# SoC_Connector.net
KiCad netlist of a schematic drawn in Altium Designer
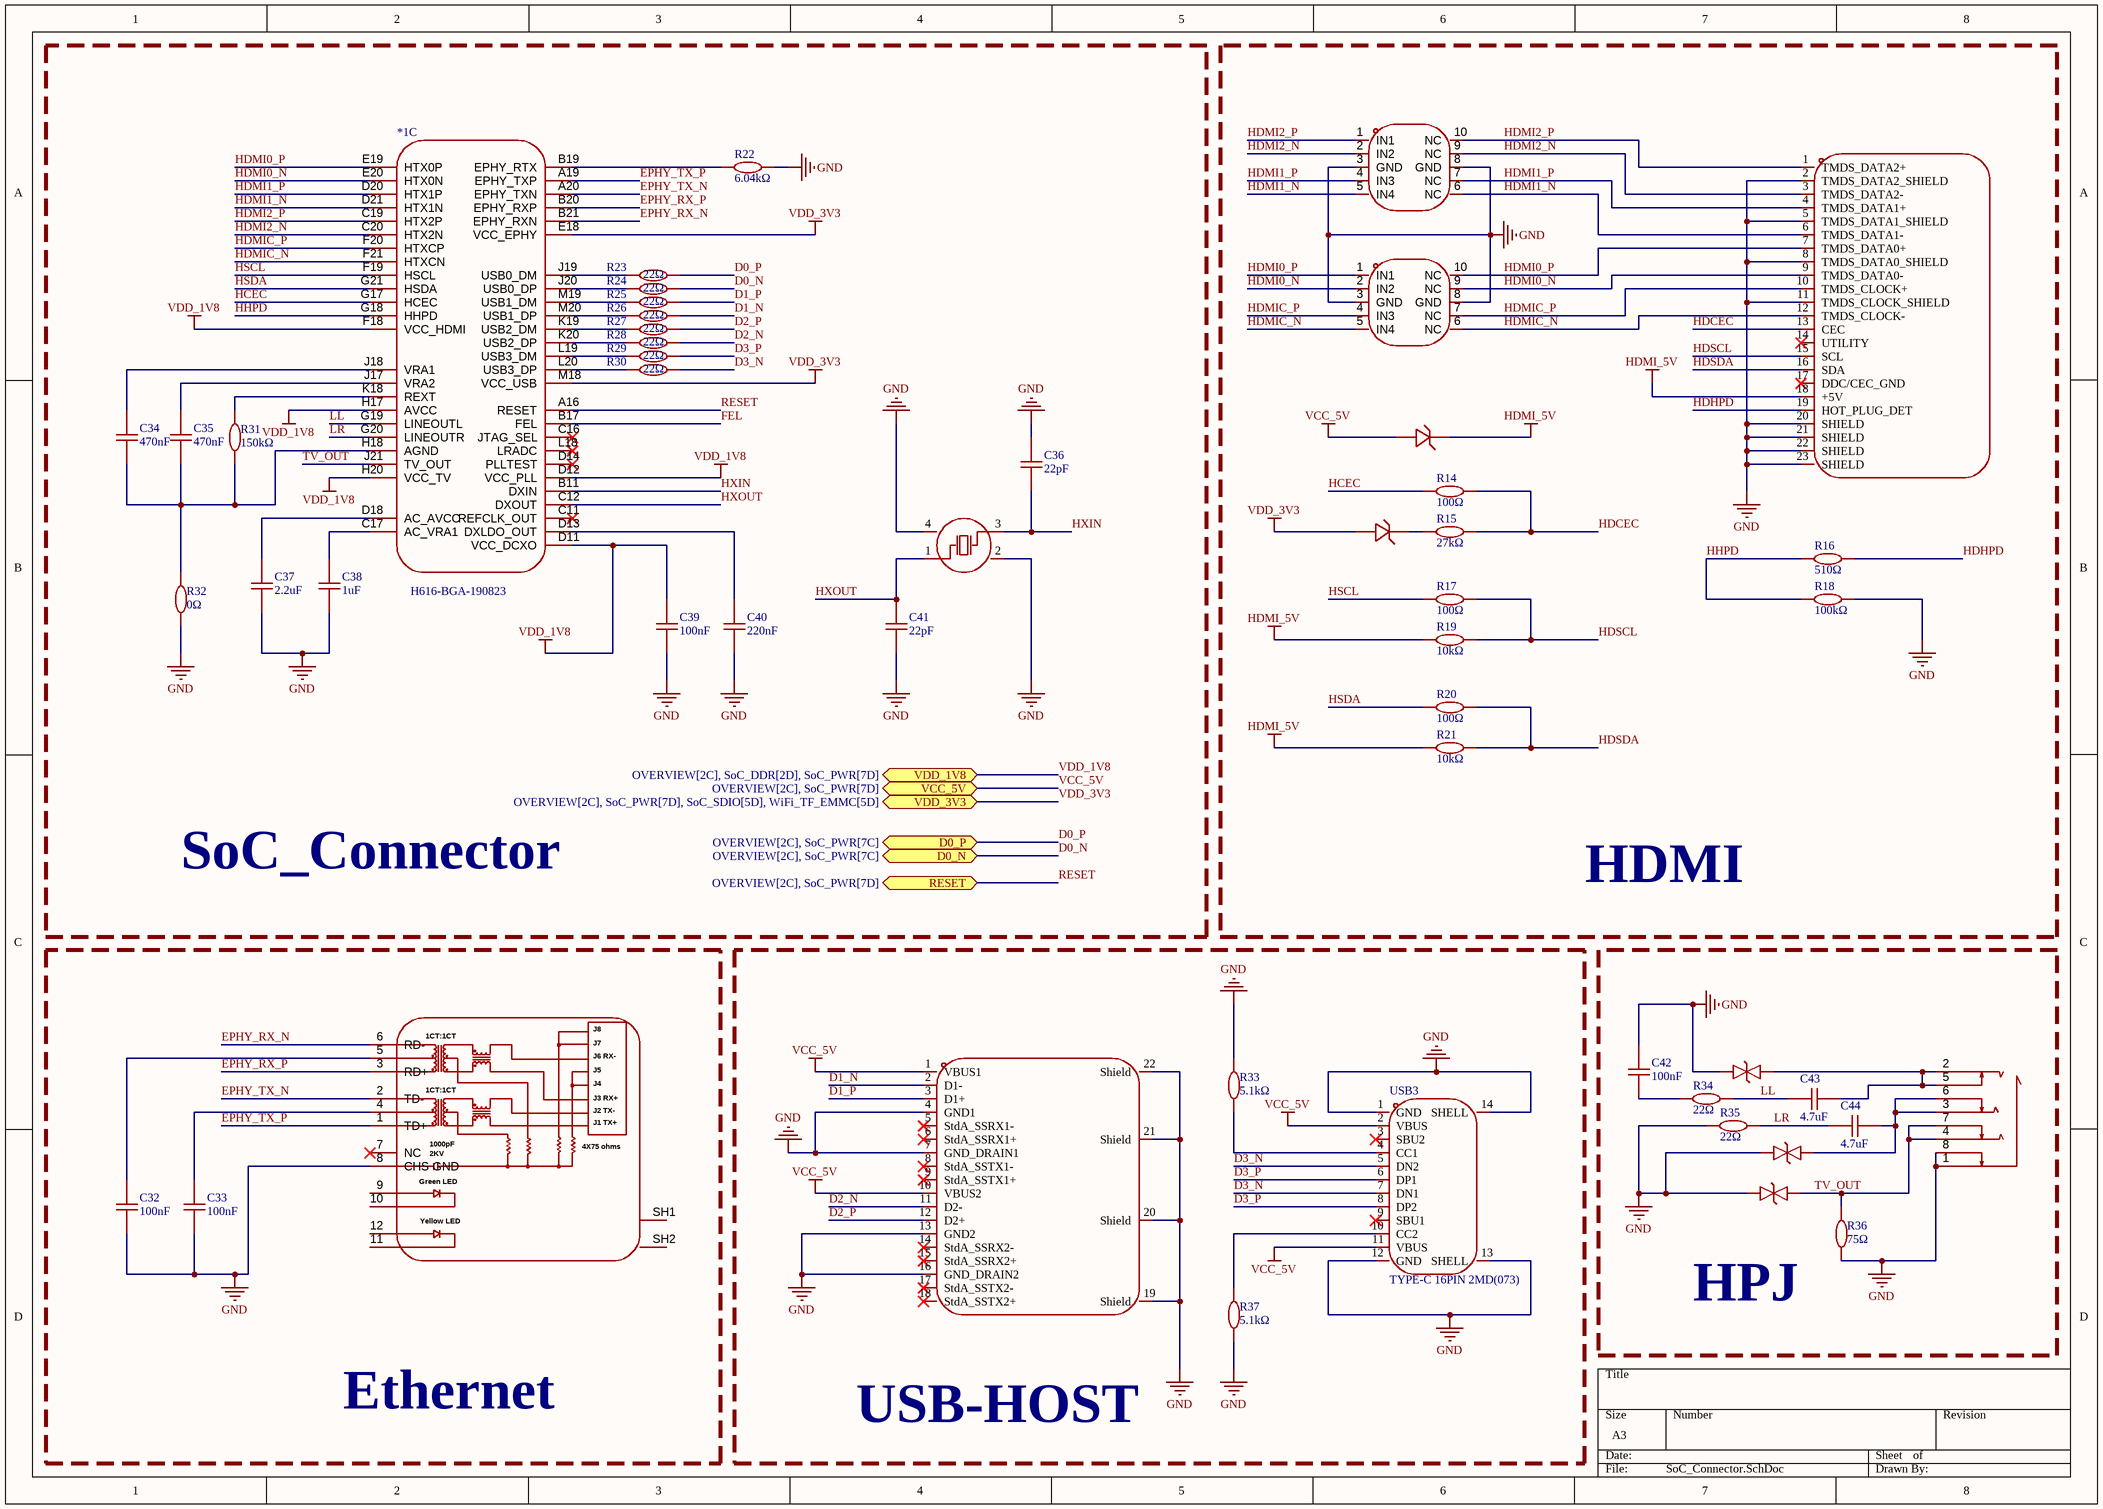
[diagram p0: SoC_Connector.SchDoc]

(export (version "E")
  (design (tool "Eeschema 10.0.6"))
  (components
    (comp (ref "*1")
      (value "H616-BGA-190823")
      (footprint "BGA-284_L14.0-W12.0-P0.65-TL")
      (description "Allwinner H616")
      (libsource (lib "IC") (part "H616-BGA-190823"))
    )
    (comp (ref "AUDIO1")
      (value "PJ-3930-8A")
      (footprint "AUDIO-TH_PJ-3930-8A")
      (description "3.5mm耳机座")
      (libsource (lib "Connector") (part "PJ-3930-8A"))
    )
    (comp (ref "C32")
      (value "100nF")
      (footprint "C0402")
      (description "50V 100nF X7R ±10% 0402 Ceramic Capacitors ROHS")
      (libsource (lib "RLC") (part "100nF"))
    )
    (comp (ref "C33")
      (value "100nF")
      (footprint "C0402")
      (description "50V 100nF X7R ±10% 0402 Ceramic Capacitors ROHS")
      (libsource (lib "RLC") (part "100nF"))
    )
    (comp (ref "C34")
      (value "470nF")
      (footprint "C0402")
      (description "25V 470nF X5R ±10% 0402 Ceramic Capacitors ROHS")
      (libsource (lib "RLC") (part "470nF"))
    )
    (comp (ref "C35")
      (value "470nF")
      (footprint "C0402")
      (description "25V 470nF X5R ±10% 0402 Ceramic Capacitors ROHS")
      (libsource (lib "RLC") (part "470nF"))
    )
    (comp (ref "C36")
      (value "22pF")
      (footprint "C0402")
      (description "50V 22pF C0G ±5% 0402 Ceramic Capacitors ROHS")
      (libsource (lib "RLC") (part "22pF"))
    )
    (comp (ref "C37")
      (value "2.2uF")
      (footprint "C0402")
      (description "50V 2.2uF NP0 0402 Ceramic Capacitors ROHS")
      (libsource (lib "RLC") (part "2.2uF"))
    )
    (comp (ref "C38")
      (value "1uF")
      (footprint "C0402")
      (description "50V 1uF X5R ±10% 0402 Ceramic Capacitors ROHS")
      (libsource (lib "RLC") (part "1uF"))
    )
    (comp (ref "C39")
      (value "100nF")
      (footprint "C0402")
      (description "50V 100nF X7R ±10% 0402 Ceramic Capacitors ROHS")
      (libsource (lib "RLC") (part "100nF"))
    )
    (comp (ref "C40")
      (value "220nF")
      (footprint "C0402")
      (description "16V 220nF X7R ±10% 0402 Ceramic Capacitors ROHS")
      (libsource (lib "RLC") (part "220nF"))
    )
    (comp (ref "C41")
      (value "22pF")
      (footprint "C0402")
      (description "50V 22pF C0G ±5% 0402 Ceramic Capacitors ROHS")
      (libsource (lib "RLC") (part "22pF"))
    )
    (comp (ref "C42")
      (value "100nF")
      (footprint "C0402")
      (description "50V 100nF X7R ±10% 0402 Ceramic Capacitors ROHS")
      (libsource (lib "RLC") (part "100nF"))
    )
    (comp (ref "C43")
      (value "4.7uF")
      (footprint "C0402")
      (description "10V 4.7uF X5R ±20% 0402 Ceramic Capacitors ROHS")
      (libsource (lib "RLC") (part "4.7uF"))
    )
    (comp (ref "C44")
      (value "4.7uF")
      (footprint "C0402")
      (description "10V 4.7uF X5R ±20% 0402 Ceramic Capacitors ROHS")
      (libsource (lib "RLC") (part "4.7uF"))
    )
    (comp (ref "CN1")
      (value "KH-HDMI-19P-Cu")
      (footprint "HDMI-SMD_KH-HDMI-19P-CU")
      (description "HDMI-A SMD USB, DVI, HDMI Connector Assemblies ROHS")
      (fields (field (name "MANUFACTURER") "kinghelm(金航标)"))
      (libsource (lib "Connector") (part "KH-HDMI-19P-Cu"))
    )
    (comp (ref "D2")
      (value "RClamp0524PATCT")
      (footprint "SLP2510P8_L2.5-W1.0-P0.50-BL")
      (description "ESD 5V截止 峰值浪涌电流：5A@8/20us")
      (libsource (lib "LED") (part "RClamp0524PATCT"))
    )
    (comp (ref "D3")
      (value "RClamp0524PATCT")
      (footprint "SLP2510P8_L2.5-W1.0-P0.50-BL")
      (description "ESD 5V截止 峰值浪涌电流：5A@8/20us")
      (libsource (lib "LED") (part "RClamp0524PATCT"))
    )
    (comp (ref "D4")
      (value "DSK24")
      (footprint "SOD-123FL_L2.7-W1.8-LS3.8-RD")
      (description "电压:40V 电流:2A")
      (fields (field (name "MANUFACTURER") "Littelfuse(美国力特)") (field (name "MANUFACTURER PART") "SMAJ5.0A"))
      (libsource (lib "LED") (part "DSK24"))
    )
    (comp (ref "D5")
      (value "DSK24")
      (footprint "SOD-123FL_L2.7-W1.8-LS3.8-RD")
      (description "电压:40V 电流:2A")
      (fields (field (name "MANUFACTURER") "Littelfuse(美国力特)") (field (name "MANUFACTURER PART") "SMAJ5.0A"))
      (libsource (lib "LED") (part "DSK24"))
    )
    (comp (ref "J1")
      (value "HR911105A_C12074")
      (footprint "RJ45-TH_HR911105A")
      (description "Ethernet 弯插 带LED")
      (libsource (lib "Connector") (part "HR911105A_C12074"))
    )
    (comp (ref "R14")
      (value "100Ω")
      (footprint "R0402")
      (description "100Ω 62.5mW 50V ±100ppm/℃ Thick Film Resistor ±1% 0402 Chip Resistor - Surface Mount ROHS")
      (libsource (lib "RLC") (part "100Ω"))
    )
    (comp (ref "R15")
      (value "27kΩ")
      (footprint "R0402")
      (description "小尺寸、重量轻。降低组装成本,与贴片机匹配。适用于波峰焊和回流焊")
      (libsource (lib "RLC") (part "27kΩ"))
    )
    (comp (ref "R16")
      (value "510Ω")
      (footprint "R0402")
      (description "510Ω 62.5mW 50V ±100ppm/℃ Thick Film Resistor ±1% 0402 Chip Resistor - Surface Mount ROHS")
      (libsource (lib "RLC") (part "510Ω"))
    )
    (comp (ref "R17")
      (value "100Ω")
      (footprint "R0402")
      (description "100Ω 62.5mW 50V ±100ppm/℃ Thick Film Resistor ±1% 0402 Chip Resistor - Surface Mount ROHS")
      (libsource (lib "RLC") (part "100Ω"))
    )
    (comp (ref "R18")
      (value "100kΩ")
      (footprint "R0402")
      (description "100kΩ 62.5mW 50V ±100ppm/℃ Thick Film Resistor ±1% 0402 Chip Resistor - Surface Mount ROHS")
      (libsource (lib "RLC") (part "100kΩ"))
    )
    (comp (ref "R19")
      (value "10kΩ")
      (footprint "R0402")
      (description "62.5mW 10kΩ 50V ±100ppm/℃ Thick Film Resistor ±1% 0402 Chip Resistor - Surface Mount ROHS")
      (libsource (lib "RLC") (part "10kΩ"))
    )
    (comp (ref "R20")
      (value "100Ω")
      (footprint "R0402")
      (description "100Ω 62.5mW 50V ±100ppm/℃ Thick Film Resistor ±1% 0402 Chip Resistor - Surface Mount ROHS")
      (libsource (lib "RLC") (part "100Ω"))
    )
    (comp (ref "R21")
      (value "10kΩ")
      (footprint "R0402")
      (description "62.5mW 10kΩ 50V ±100ppm/℃ Thick Film Resistor ±1% 0402 Chip Resistor - Surface Mount ROHS")
      (libsource (lib "RLC") (part "10kΩ"))
    )
    (comp (ref "R22")
      (value "6.04kΩ")
      (footprint "R0402")
      (description "6.04kΩ 62.5mW 50V ±100ppm/℃ Thick Film Resistor ±1% 0402 Chip Resistor - Surface Mount ROHS")
      (libsource (lib "RLC") (part "6.04kΩ"))
    )
    (comp (ref "R23")
      (value "22Ω")
      (footprint "R0402")
      (description "小尺寸、重量轻。降低组装成本,与贴片机匹配。适用于波峰焊和回流焊")
      (libsource (lib "RLC") (part "22Ω"))
    )
    (comp (ref "R24")
      (value "22Ω")
      (footprint "R0402")
      (description "小尺寸、重量轻。降低组装成本,与贴片机匹配。适用于波峰焊和回流焊")
      (libsource (lib "RLC") (part "22Ω"))
    )
    (comp (ref "R25")
      (value "22Ω")
      (footprint "R0402")
      (description "小尺寸、重量轻。降低组装成本,与贴片机匹配。适用于波峰焊和回流焊")
      (libsource (lib "RLC") (part "22Ω"))
    )
    (comp (ref "R26")
      (value "22Ω")
      (footprint "R0402")
      (description "小尺寸、重量轻。降低组装成本,与贴片机匹配。适用于波峰焊和回流焊")
      (libsource (lib "RLC") (part "22Ω"))
    )
    (comp (ref "R27")
      (value "22Ω")
      (footprint "R0402")
      (description "小尺寸、重量轻。降低组装成本,与贴片机匹配。适用于波峰焊和回流焊")
      (libsource (lib "RLC") (part "22Ω"))
    )
    (comp (ref "R28")
      (value "22Ω")
      (footprint "R0402")
      (description "小尺寸、重量轻。降低组装成本,与贴片机匹配。适用于波峰焊和回流焊")
      (libsource (lib "RLC") (part "22Ω"))
    )
    (comp (ref "R29")
      (value "22Ω")
      (footprint "R0402")
      (description "小尺寸、重量轻。降低组装成本,与贴片机匹配。适用于波峰焊和回流焊")
      (libsource (lib "RLC") (part "22Ω"))
    )
    (comp (ref "R30")
      (value "22Ω")
      (footprint "R0402")
      (description "小尺寸、重量轻。降低组装成本,与贴片机匹配。适用于波峰焊和回流焊")
      (libsource (lib "RLC") (part "22Ω"))
    )
    (comp (ref "R31")
      (value "150kΩ")
      (footprint "R0402")
      (description "62.5mW 150kΩ 50V ±100ppm/℃ Thick Film Resistor ±1% 0402 Chip Resistor - Surface Mount ROHS")
      (libsource (lib "RLC") (part "150kΩ"))
    )
    (comp (ref "R32")
      (value "0Ω")
      (footprint "R0402")
      (description "0Ω 62.5mW 50V Thick Film Resistor ±1% 0402 Chip Resistor - Surface Mount ROHS")
      (libsource (lib "RLC") (part "0Ω"))
    )
    (comp (ref "R33")
      (value "5.1kΩ")
      (footprint "R0402")
      (description "5.1kΩ 62.5mW 50V ±100ppm/℃ Thick Film Resistor ±1% 0402 Chip Resistor - Surface Mount ROHS")
      (libsource (lib "RLC") (part "5.1kΩ"))
    )
    (comp (ref "R34")
      (value "22Ω")
      (footprint "R0402")
      (description "小尺寸、重量轻。降低组装成本,与贴片机匹配。适用于波峰焊和回流焊")
      (libsource (lib "RLC") (part "22Ω"))
    )
    (comp (ref "R35")
      (value "22Ω")
      (footprint "R0402")
      (description "小尺寸、重量轻。降低组装成本,与贴片机匹配。适用于波峰焊和回流焊")
      (libsource (lib "RLC") (part "22Ω"))
    )
    (comp (ref "R36")
      (value "75Ω")
      (footprint "R0402")
      (description "小尺寸、重量轻。降低组装成本,与贴片机匹配。适用于波峰焊和回流焊")
      (libsource (lib "RLC") (part "75Ω"))
    )
    (comp (ref "R37")
      (value "5.1kΩ")
      (footprint "R0402")
      (description "5.1kΩ 62.5mW 50V ±100ppm/℃ Thick Film Resistor ±1% 0402 Chip Resistor - Surface Mount ROHS")
      (libsource (lib "RLC") (part "5.1kΩ"))
    )
    (comp (ref "U3")
      (value "ESD5451N")
      (footprint "DFN1006-2L-BI")
      (description "9A 9.8V 8V Bidirectional 5V DFN1006-2L TVS Diodes ROHS")
      (fields (field (name "MANUFACTURER") "HXY MOSFET(华轩阳电子)"))
      (libsource (lib "LED") (part "ESD5451N_C5261080"))
    )
    (comp (ref "U4")
      (value "ESD5451N")
      (footprint "DFN1006-2L-BI")
      (description "9A 9.8V 8V Bidirectional 5V DFN1006-2L TVS Diodes ROHS")
      (fields (field (name "MANUFACTURER") "HXY MOSFET(华轩阳电子)"))
      (libsource (lib "LED") (part "ESD5451N_C5261080"))
    )
    (comp (ref "U5")
      (value "ESD5451N")
      (footprint "DFN1006-2L-BI")
      (description "9A 9.8V 8V Bidirectional 5V DFN1006-2L TVS Diodes ROHS")
      (fields (field (name "MANUFACTURER") "HXY MOSFET(华轩阳电子)"))
      (libsource (lib "LED") (part "ESD5451N_C5261080"))
    )
    (comp (ref "USB2")
      (value "USB-303WSD-BRY")
      (footprint "USB-A-TH_XUNPU_USB-303WSD-BRY")
      (description "USB 3.0 2 9Px2 -30℃~+85℃ Type-A Through Hole,Right Angle USB, DVI, HDMI Connector Assemblies ROHS")
      (fields (field (name "MANUFACTURER") "XUNPU(讯普)"))
      (libsource (lib "Connector") (part "USB-303WSD-BRY"))
    )
    (comp (ref "USB3")
      (value "TYPE-C 16PIN 2MD(073)")
      (footprint "USB-C-SMD_TYPE-C-6PIN-2MD-073")
      (description "16pin type-c")
      (libsource (lib "Connector") (part "TYPE-C 16PIN 2MD(073)"))
    )
    (comp (ref "X1")
      (value "24MHz")
      (footprint "CRYSTAL-SMD_4P-L3.2-W2.5-BL")
      (description "Crystal Oscillator 12pF SMD3225-4P Crystals ROHS")
      (fields (field (name "MANUFACTURER") "YXC(扬兴晶振)") (field (name "MANUFACTURER PART") "X322524MOB4SI"))
      (libsource (lib "OSC") (part "X322524MOB4SI"))
    )
  )
  (nets
    (net (code "1") (name "/D0_N") (class "Default")
      (node (ref "R24") (pin "2") (pinfunction "2_2") (pintype "passive"))
    )
    (net (code "2") (name "/D0_P") (class "Default")
      (node (ref "R23") (pin "2") (pinfunction "2_2") (pintype "passive"))
    )
    (net (code "3") (name "/D1_N") (class "Default")
      (node (ref "R26") (pin "2") (pinfunction "2_2") (pintype "passive"))
      (node (ref "USB2") (pin "2") (pinfunction "D1-_2") (pintype "passive"))
    )
    (net (code "4") (name "/D1_P") (class "Default")
      (node (ref "R25") (pin "2") (pinfunction "2_2") (pintype "passive"))
      (node (ref "USB2") (pin "3") (pinfunction "D1+_3") (pintype "passive"))
    )
    (net (code "5") (name "/D2_N") (class "Default")
      (node (ref "R28") (pin "2") (pinfunction "2_2") (pintype "passive"))
      (node (ref "USB2") (pin "11") (pinfunction "D2-_11") (pintype "passive"))
    )
    (net (code "6") (name "/D2_P") (class "Default")
      (node (ref "R27") (pin "2") (pinfunction "2_2") (pintype "passive"))
      (node (ref "USB2") (pin "12") (pinfunction "D2+_12") (pintype "passive"))
    )
    (net (code "7") (name "/D3_N") (class "Default")
      (node (ref "R30") (pin "2") (pinfunction "2_2") (pintype "passive"))
      (node (ref "USB3") (pin "5") (pinfunction "DN2_5") (pintype "passive"))
      (node (ref "USB3") (pin "7") (pinfunction "DN1_7") (pintype "passive"))
    )
    (net (code "8") (name "/D3_P") (class "Default")
      (node (ref "R29") (pin "2") (pinfunction "2_2") (pintype "passive"))
      (node (ref "USB3") (pin "6") (pinfunction "DP1_6") (pintype "passive"))
      (node (ref "USB3") (pin "8") (pinfunction "DP2_8") (pintype "passive"))
    )
    (net (code "9") (name "/EPHY_RX_N") (class "Default")
      (node (ref "*1") (pin "B21") (pinfunction "EPHY_RXN_B21") (pintype "passive"))
      (node (ref "J1") (pin "6") (pinfunction "RD-_6") (pintype "passive"))
    )
    (net (code "10") (name "/EPHY_RX_P") (class "Default")
      (node (ref "*1") (pin "B20") (pinfunction "EPHY_RXP_B20") (pintype "passive"))
      (node (ref "J1") (pin "3") (pinfunction "RD+_3") (pintype "passive"))
    )
    (net (code "11") (name "/EPHY_TX_N") (class "Default")
      (node (ref "*1") (pin "A20") (pinfunction "EPHY_TXN_A20") (pintype "passive"))
      (node (ref "J1") (pin "2") (pinfunction "TD-_2") (pintype "passive"))
    )
    (net (code "12") (name "/EPHY_TX_P") (class "Default")
      (node (ref "*1") (pin "A19") (pinfunction "EPHY_TXP_A19") (pintype "passive"))
      (node (ref "J1") (pin "1") (pinfunction "TD+_1") (pintype "passive"))
    )
    (net (code "13") (name "/FEL") (class "Default")
      (node (ref "*1") (pin "B17") (pinfunction "FEL_B17") (pintype "passive"))
    )
    (net (code "14") (name "/HCEC") (class "Default")
      (node (ref "*1") (pin "G17") (pinfunction "HCEC_G17") (pintype "passive"))
      (node (ref "R14") (pin "1") (pinfunction "1_1") (pintype "passive"))
    )
    (net (code "15") (name "/HDCEC") (class "Default")
      (node (ref "CN1") (pin "13") (pinfunction "CEC_13") (pintype "passive"))
      (node (ref "R14") (pin "2") (pinfunction "2_2") (pintype "passive"))
      (node (ref "R15") (pin "2") (pinfunction "2_2") (pintype "passive"))
    )
    (net (code "16") (name "/HDHPD") (class "Default")
      (node (ref "CN1") (pin "19") (pinfunction "HOT_PLUG_DET_19") (pintype "passive"))
      (node (ref "R16") (pin "2") (pinfunction "2_2") (pintype "passive"))
    )
    (net (code "17") (name "/HDMI0_N") (class "Default")
      (node (ref "*1") (pin "E20") (pinfunction "HTX0N_E20") (pintype "passive"))
      (node (ref "CN1") (pin "9") (pinfunction "TMDS_DATA0-_9") (pintype "passive"))
      (node (ref "D3") (pin "2") (pinfunction "IN2_2") (pintype "passive"))
      (node (ref "D3") (pin "9") (pinfunction "NC_9") (pintype "passive"))
    )
    (net (code "18") (name "/HDMI0_P") (class "Default")
      (node (ref "*1") (pin "E19") (pinfunction "HTX0P_E19") (pintype "passive"))
      (node (ref "CN1") (pin "7") (pinfunction "TMDS_DATA0+_7") (pintype "passive"))
      (node (ref "D3") (pin "1") (pinfunction "IN1_1") (pintype "passive"))
      (node (ref "D3") (pin "10") (pinfunction "NC_10") (pintype "passive"))
    )
    (net (code "19") (name "/HDMI1_N") (class "Default")
      (node (ref "*1") (pin "D21") (pinfunction "HTX1N_D21") (pintype "passive"))
      (node (ref "CN1") (pin "6") (pinfunction "TMDS_DATA1-_6") (pintype "passive"))
      (node (ref "D2") (pin "5") (pinfunction "IN4_5") (pintype "passive"))
      (node (ref "D2") (pin "6") (pinfunction "NC_6") (pintype "passive"))
    )
    (net (code "20") (name "/HDMI1_P") (class "Default")
      (node (ref "*1") (pin "D20") (pinfunction "HTX1P_D20") (pintype "passive"))
      (node (ref "CN1") (pin "4") (pinfunction "TMDS_DATA1+_4") (pintype "passive"))
      (node (ref "D2") (pin "4") (pinfunction "IN3_4") (pintype "passive"))
      (node (ref "D2") (pin "7") (pinfunction "NC_7") (pintype "passive"))
    )
    (net (code "21") (name "/HDMI2_N") (class "Default")
      (node (ref "*1") (pin "C20") (pinfunction "HTX2N_C20") (pintype "passive"))
      (node (ref "CN1") (pin "3") (pinfunction "TMDS_DATA2-_3") (pintype "passive"))
      (node (ref "D2") (pin "2") (pinfunction "IN2_2") (pintype "passive"))
      (node (ref "D2") (pin "9") (pinfunction "NC_9") (pintype "passive"))
    )
    (net (code "22") (name "/HDMI2_P") (class "Default")
      (node (ref "*1") (pin "C19") (pinfunction "HTX2P_C19") (pintype "passive"))
      (node (ref "CN1") (pin "1") (pinfunction "TMDS_DATA2+_1") (pintype "passive"))
      (node (ref "D2") (pin "1") (pinfunction "IN1_1") (pintype "passive"))
      (node (ref "D2") (pin "10") (pinfunction "NC_10") (pintype "passive"))
    )
    (net (code "23") (name "/HDMIC_N") (class "Default")
      (node (ref "*1") (pin "F21") (pinfunction "HTXCN_F21") (pintype "passive"))
      (node (ref "CN1") (pin "12") (pinfunction "TMDS_CLOCK-_12") (pintype "passive"))
      (node (ref "D3") (pin "5") (pinfunction "IN4_5") (pintype "passive"))
      (node (ref "D3") (pin "6") (pinfunction "NC_6") (pintype "passive"))
    )
    (net (code "24") (name "/HDMIC_P") (class "Default")
      (node (ref "*1") (pin "F20") (pinfunction "HTXCP_F20") (pintype "passive"))
      (node (ref "CN1") (pin "10") (pinfunction "TMDS_CLOCK+_10") (pintype "passive"))
      (node (ref "D3") (pin "4") (pinfunction "IN3_4") (pintype "passive"))
      (node (ref "D3") (pin "7") (pinfunction "NC_7") (pintype "passive"))
    )
    (net (code "25") (name "/HDSCL") (class "Default")
      (node (ref "CN1") (pin "15") (pinfunction "SCL_15") (pintype "passive"))
      (node (ref "R17") (pin "2") (pinfunction "2_2") (pintype "passive"))
      (node (ref "R19") (pin "2") (pinfunction "2_2") (pintype "passive"))
    )
    (net (code "26") (name "/HDSDA") (class "Default")
      (node (ref "CN1") (pin "16") (pinfunction "SDA_16") (pintype "passive"))
      (node (ref "R20") (pin "2") (pinfunction "2_2") (pintype "passive"))
      (node (ref "R21") (pin "2") (pinfunction "2_2") (pintype "passive"))
    )
    (net (code "27") (name "/HHPD") (class "Default")
      (node (ref "*1") (pin "G18") (pinfunction "HHPD_G18") (pintype "passive"))
      (node (ref "R16") (pin "1") (pinfunction "1_1") (pintype "passive"))
      (node (ref "R18") (pin "1") (pinfunction "1_1") (pintype "passive"))
    )
    (net (code "28") (name "/HSCL") (class "Default")
      (node (ref "*1") (pin "F19") (pinfunction "HSCL_F19") (pintype "passive"))
      (node (ref "R17") (pin "1") (pinfunction "1_1") (pintype "passive"))
    )
    (net (code "29") (name "/HSDA") (class "Default")
      (node (ref "*1") (pin "G21") (pinfunction "HSDA_G21") (pintype "passive"))
      (node (ref "R20") (pin "1") (pinfunction "1_1") (pintype "passive"))
    )
    (net (code "30") (name "/HXIN") (class "Default")
      (node (ref "*1") (pin "B11") (pinfunction "DXIN_B11") (pintype "passive"))
      (node (ref "C36") (pin "1") (pinfunction "1_1") (pintype "passive"))
      (node (ref "X1") (pin "3") (pinfunction "OSC2_3") (pintype "passive"))
    )
    (net (code "31") (name "/HXOUT") (class "Default")
      (node (ref "*1") (pin "C12") (pinfunction "DXOUT_C12") (pintype "passive"))
      (node (ref "C41") (pin "2") (pinfunction "2_2") (pintype "passive"))
      (node (ref "X1") (pin "1") (pinfunction "OSC1_1") (pintype "passive"))
    )
    (net (code "32") (name "/LL") (class "Default")
      (node (ref "*1") (pin "G19") (pinfunction "LINEOUTL_G19") (pintype "passive"))
      (node (ref "C43") (pin "1") (pinfunction "1_1") (pintype "passive"))
      (node (ref "R34") (pin "2") (pinfunction "2_2") (pintype "passive"))
    )
    (net (code "33") (name "/LR") (class "Default")
      (node (ref "*1") (pin "G20") (pinfunction "LINEOUTR_G20") (pintype "passive"))
      (node (ref "C44") (pin "1") (pinfunction "1_1") (pintype "passive"))
      (node (ref "R35") (pin "2") (pinfunction "2_2") (pintype "passive"))
    )
    (net (code "34") (name "/RESET") (class "Default")
      (node (ref "*1") (pin "A16") (pinfunction "RESET_A16") (pintype "passive"))
    )
    (net (code "35") (name "/TV_OUT") (class "Default")
      (node (ref "*1") (pin "J21") (pinfunction "TV_OUT_J21") (pintype "passive"))
      (node (ref "AUDIO1") (pin "4") (pinfunction "4_4") (pintype "passive"))
      (node (ref "AUDIO1") (pin "7") (pinfunction "7_7") (pintype "passive"))
      (node (ref "R36") (pin "2") (pinfunction "2_2") (pintype "passive"))
      (node (ref "U5") (pin "2") (pinfunction "2_2") (pintype "passive"))
    )
    (net (code "36") (name "GND") (class "Default")
      (node (ref "AUDIO1") (pin "1") (pinfunction "1_1") (pintype "passive"))
      (node (ref "AUDIO1") (pin "8") (pinfunction "8_8") (pintype "passive"))
      (node (ref "C32") (pin "1") (pinfunction "1_1") (pintype "passive"))
      (node (ref "C33") (pin "1") (pinfunction "1_1") (pintype "passive"))
      (node (ref "C36") (pin "2") (pinfunction "2_2") (pintype "passive"))
      (node (ref "C37") (pin "1") (pinfunction "1_1") (pintype "passive"))
      (node (ref "C38") (pin "1") (pinfunction "1_1") (pintype "passive"))
      (node (ref "C39") (pin "1") (pinfunction "1_1") (pintype "passive"))
      (node (ref "C40") (pin "1") (pinfunction "1_1") (pintype "passive"))
      (node (ref "C41") (pin "1") (pinfunction "1_1") (pintype "passive"))
      (node (ref "C42") (pin "2") (pinfunction "2_2") (pintype "passive"))
      (node (ref "CN1") (pin "11") (pinfunction "TMDS_CLOCK_SHIELD_11") (pintype "passive"))
      (node (ref "CN1") (pin "2") (pinfunction "TMDS_DATA2_SHIELD_2") (pintype "passive"))
      (node (ref "CN1") (pin "20") (pinfunction "SHIELD_20") (pintype "passive"))
      (node (ref "CN1") (pin "21") (pinfunction "SHIELD_21") (pintype "passive"))
      (node (ref "CN1") (pin "22") (pinfunction "SHIELD_22") (pintype "passive"))
      (node (ref "CN1") (pin "23") (pinfunction "SHIELD_23") (pintype "passive"))
      (node (ref "CN1") (pin "5") (pinfunction "TMDS_DATA1_SHIELD_5") (pintype "passive"))
      (node (ref "CN1") (pin "8") (pinfunction "TMDS_DATA0_SHIELD_8") (pintype "passive"))
      (node (ref "D2") (pin "3") (pinfunction "GND_3") (pintype "passive"))
      (node (ref "D2") (pin "8") (pinfunction "GND_8") (pintype "passive"))
      (node (ref "D3") (pin "3") (pinfunction "GND_3") (pintype "passive"))
      (node (ref "D3") (pin "8") (pinfunction "GND_8") (pintype "passive"))
      (node (ref "J1") (pin "8") (pinfunction "CHS_GND_8") (pintype "passive"))
      (node (ref "R18") (pin "2") (pinfunction "2_2") (pintype "passive"))
      (node (ref "R22") (pin "2") (pinfunction "2_2") (pintype "passive"))
      (node (ref "R32") (pin "1") (pinfunction "1_1") (pintype "passive"))
      (node (ref "R33") (pin "2") (pinfunction "2_2") (pintype "passive"))
      (node (ref "R35") (pin "1") (pinfunction "1_1") (pintype "passive"))
      (node (ref "R36") (pin "1") (pinfunction "1_1") (pintype "passive"))
      (node (ref "R37") (pin "2") (pinfunction "2_2") (pintype "passive"))
      (node (ref "U3") (pin "1") (pinfunction "1_1") (pintype "passive"))
      (node (ref "U4") (pin "1") (pinfunction "1_1") (pintype "passive"))
      (node (ref "U5") (pin "1") (pinfunction "1_1") (pintype "passive"))
      (node (ref "USB2") (pin "13") (pinfunction "GND2_13") (pintype "passive"))
      (node (ref "USB2") (pin "16") (pinfunction "GND_DRAIN2_16") (pintype "passive"))
      (node (ref "USB2") (pin "19") (pinfunction "Shield_19") (pintype "passive"))
      (node (ref "USB2") (pin "20") (pinfunction "Shield_20") (pintype "passive"))
      (node (ref "USB2") (pin "21") (pinfunction "Shield_21") (pintype "passive"))
      (node (ref "USB2") (pin "22") (pinfunction "Shield_22") (pintype "passive"))
      (node (ref "USB2") (pin "4") (pinfunction "GND1_4") (pintype "passive"))
      (node (ref "USB2") (pin "7") (pinfunction "GND_DRAIN1_7") (pintype "passive"))
      (node (ref "USB3") (pin "1") (pinfunction "GND_1") (pintype "passive"))
      (node (ref "USB3") (pin "12") (pinfunction "GND_12") (pintype "passive"))
      (node (ref "USB3") (pin "13") (pinfunction "SHELL_13") (pintype "passive"))
      (node (ref "USB3") (pin "14") (pinfunction "SHELL_14") (pintype "passive"))
      (node (ref "X1") (pin "2") (pinfunction "GND_2") (pintype "passive"))
      (node (ref "X1") (pin "4") (pinfunction "GND_4") (pintype "passive"))
    )
    (net (code "37") (name "HDMI_5V") (class "Default")
      (node (ref "CN1") (pin "18") (pinfunction "+5V_18") (pintype "passive"))
      (node (ref "D4") (pin "1") (pinfunction "C_1") (pintype "passive"))
      (node (ref "R19") (pin "1") (pinfunction "1_1") (pintype "passive"))
      (node (ref "R21") (pin "1") (pinfunction "1_1") (pintype "passive"))
    )
    (net (code "38") (name "Net-(*1C-AC_AVCC)") (class "Default")
      (node (ref "*1") (pin "D18") (pinfunction "AC_AVCC_D18") (pintype "passive"))
      (node (ref "C37") (pin "2") (pinfunction "2_2") (pintype "passive"))
    )
    (net (code "39") (name "Net-(*1C-AC_VRA1)") (class "Default")
      (node (ref "*1") (pin "C17") (pinfunction "AC_VRA1_C17") (pintype "passive"))
      (node (ref "C38") (pin "2") (pinfunction "2_2") (pintype "passive"))
    )
    (net (code "40") (name "Net-(*1C-AGND)") (class "Default")
      (node (ref "*1") (pin "H18") (pinfunction "AGND_H18") (pintype "passive"))
      (node (ref "C34") (pin "1") (pinfunction "1_1") (pintype "passive"))
      (node (ref "C35") (pin "1") (pinfunction "1_1") (pintype "passive"))
      (node (ref "R31") (pin "1") (pinfunction "1_1") (pintype "passive"))
      (node (ref "R32") (pin "2") (pinfunction "2_2") (pintype "passive"))
    )
    (net (code "41") (name "Net-(*1C-DXLDO_OUT)") (class "Default")
      (node (ref "*1") (pin "D13") (pinfunction "DXLDO_OUT_D13") (pintype "passive"))
      (node (ref "C40") (pin "2") (pinfunction "2_2") (pintype "passive"))
    )
    (net (code "42") (name "Net-(*1C-EPHY_RTX)") (class "Default")
      (node (ref "*1") (pin "B19") (pinfunction "EPHY_RTX_B19") (pintype "passive"))
      (node (ref "R22") (pin "1") (pinfunction "1_1") (pintype "passive"))
    )
    (net (code "43") (name "Net-(*1C-REXT)") (class "Default")
      (node (ref "*1") (pin "K18") (pinfunction "REXT_K18") (pintype "passive"))
      (node (ref "R31") (pin "2") (pinfunction "2_2") (pintype "passive"))
    )
    (net (code "44") (name "Net-(*1C-USB0_DM)") (class "Default")
      (node (ref "*1") (pin "J19") (pinfunction "USB0_DM_J19") (pintype "passive"))
      (node (ref "R23") (pin "1") (pinfunction "1_1") (pintype "passive"))
    )
    (net (code "45") (name "Net-(*1C-USB0_DP)") (class "Default")
      (node (ref "*1") (pin "J20") (pinfunction "USB0_DP_J20") (pintype "passive"))
      (node (ref "R24") (pin "1") (pinfunction "1_1") (pintype "passive"))
    )
    (net (code "46") (name "Net-(*1C-USB1_DM)") (class "Default")
      (node (ref "*1") (pin "M19") (pinfunction "USB1_DM_M19") (pintype "passive"))
      (node (ref "R25") (pin "1") (pinfunction "1_1") (pintype "passive"))
    )
    (net (code "47") (name "Net-(*1C-USB1_DP)") (class "Default")
      (node (ref "*1") (pin "M20") (pinfunction "USB1_DP_M20") (pintype "passive"))
      (node (ref "R26") (pin "1") (pinfunction "1_1") (pintype "passive"))
    )
    (net (code "48") (name "Net-(*1C-USB2_DM)") (class "Default")
      (node (ref "*1") (pin "K19") (pinfunction "USB2_DM_K19") (pintype "passive"))
      (node (ref "R27") (pin "1") (pinfunction "1_1") (pintype "passive"))
    )
    (net (code "49") (name "Net-(*1C-USB2_DP)") (class "Default")
      (node (ref "*1") (pin "K20") (pinfunction "USB2_DP_K20") (pintype "passive"))
      (node (ref "R28") (pin "1") (pinfunction "1_1") (pintype "passive"))
    )
    (net (code "50") (name "Net-(*1C-USB3_DM)") (class "Default")
      (node (ref "*1") (pin "L19") (pinfunction "USB3_DM_L19") (pintype "passive"))
      (node (ref "R29") (pin "1") (pinfunction "1_1") (pintype "passive"))
    )
    (net (code "51") (name "Net-(*1C-USB3_DP)") (class "Default")
      (node (ref "*1") (pin "L20") (pinfunction "USB3_DP_L20") (pintype "passive"))
      (node (ref "R30") (pin "1") (pinfunction "1_1") (pintype "passive"))
    )
    (net (code "52") (name "Net-(*1C-VRA1)") (class "Default")
      (node (ref "*1") (pin "J18") (pinfunction "VRA1_J18") (pintype "passive"))
      (node (ref "C34") (pin "2") (pinfunction "2_2") (pintype "passive"))
    )
    (net (code "53") (name "Net-(*1C-VRA2)") (class "Default")
      (node (ref "*1") (pin "J17") (pinfunction "VRA2_J17") (pintype "passive"))
      (node (ref "C35") (pin "2") (pinfunction "2_2") (pintype "passive"))
    )
    (net (code "54") (name "Net-(AUDIO1-Pad2)") (class "Default")
      (node (ref "AUDIO1") (pin "2") (pinfunction "2_2") (pintype "passive"))
      (node (ref "AUDIO1") (pin "5") (pinfunction "5_5") (pintype "passive"))
      (node (ref "C43") (pin "2") (pinfunction "2_2") (pintype "passive"))
      (node (ref "U3") (pin "2") (pinfunction "2_2") (pintype "passive"))
    )
    (net (code "55") (name "Net-(AUDIO1-Pad3)") (class "Default")
      (node (ref "AUDIO1") (pin "3") (pinfunction "3_3") (pintype "passive"))
      (node (ref "AUDIO1") (pin "6") (pinfunction "6_6") (pintype "passive"))
      (node (ref "C44") (pin "2") (pinfunction "2_2") (pintype "passive"))
      (node (ref "U4") (pin "2") (pinfunction "2_2") (pintype "passive"))
    )
    (net (code "56") (name "Net-(C32-Pad2)") (class "Default")
      (node (ref "C32") (pin "2") (pinfunction "2_2") (pintype "passive"))
      (node (ref "J1") (pin "5") (pinfunction "5_5") (pintype "passive"))
    )
    (net (code "57") (name "Net-(C33-Pad2)") (class "Default")
      (node (ref "C33") (pin "2") (pinfunction "2_2") (pintype "passive"))
      (node (ref "J1") (pin "4") (pinfunction "4_4") (pintype "passive"))
    )
    (net (code "58") (name "Net-(C42-Pad1)") (class "Default")
      (node (ref "C42") (pin "1") (pinfunction "1_1") (pintype "passive"))
      (node (ref "R34") (pin "1") (pinfunction "1_1") (pintype "passive"))
    )
    (net (code "59") (name "Net-(D5-C)") (class "Default")
      (node (ref "D5") (pin "1") (pinfunction "C_1") (pintype "passive"))
      (node (ref "R15") (pin "1") (pinfunction "1_1") (pintype "passive"))
    )
    (net (code "60") (name "Net-(USB3-CC1)") (class "Default")
      (node (ref "R33") (pin "1") (pinfunction "1_1") (pintype "passive"))
      (node (ref "USB3") (pin "4") (pinfunction "CC1_4") (pintype "passive"))
    )
    (net (code "61") (name "Net-(USB3-CC2)") (class "Default")
      (node (ref "R37") (pin "1") (pinfunction "1_1") (pintype "passive"))
      (node (ref "USB3") (pin "10") (pinfunction "CC2_10") (pintype "passive"))
    )
    (net (code "62") (name "VCC_5V") (class "Default")
      (node (ref "D4") (pin "2") (pinfunction "A_2") (pintype "passive"))
      (node (ref "USB2") (pin "1") (pinfunction "VBUS1_1") (pintype "passive"))
      (node (ref "USB2") (pin "10") (pinfunction "VBUS2_10") (pintype "passive"))
      (node (ref "USB3") (pin "11") (pinfunction "VBUS_11") (pintype "passive"))
      (node (ref "USB3") (pin "2") (pinfunction "VBUS_2") (pintype "passive"))
    )
    (net (code "63") (name "VDD_1V8") (class "Default")
      (node (ref "*1") (pin "D11") (pinfunction "VCC_DCXO_D11") (pintype "passive"))
      (node (ref "*1") (pin "D12") (pinfunction "VCC_PLL_D12") (pintype "passive"))
      (node (ref "*1") (pin "F18") (pinfunction "VCC_HDMI_F18") (pintype "passive"))
      (node (ref "*1") (pin "H17") (pinfunction "AVCC_H17") (pintype "passive"))
      (node (ref "*1") (pin "H20") (pinfunction "VCC_TV_H20") (pintype "passive"))
      (node (ref "C39") (pin "2") (pinfunction "2_2") (pintype "passive"))
    )
    (net (code "64") (name "VDD_3V3") (class "Default")
      (node (ref "*1") (pin "E18") (pinfunction "VCC_EPHY_E18") (pintype "passive"))
      (node (ref "*1") (pin "M18") (pinfunction "VCC_USB_M18") (pintype "passive"))
      (node (ref "D5") (pin "2") (pinfunction "A_2") (pintype "passive"))
    )
    (net (code "65") (name "unconnected-(*1C-JTAG_SEL-PadC16)") (class "Default")
      (node (ref "*1") (pin "C16") (pinfunction "JTAG_SEL_C16") (pintype "passive+no_connect"))
    )
    (net (code "66") (name "unconnected-(*1C-LRADC-PadL18)") (class "Default")
      (node (ref "*1") (pin "L18") (pinfunction "LRADC_L18") (pintype "passive+no_connect"))
    )
    (net (code "67") (name "unconnected-(*1C-PLLTEST-PadD14)") (class "Default")
      (node (ref "*1") (pin "D14") (pinfunction "PLLTEST_D14") (pintype "passive+no_connect"))
    )
    (net (code "68") (name "unconnected-(*1C-REFCLK_OUT-PadC11)") (class "Default")
      (node (ref "*1") (pin "C11") (pinfunction "REFCLK_OUT_C11") (pintype "passive+no_connect"))
    )
    (net (code "69") (name "unconnected-(CN1-DDC{slash}CEC_GND-Pad17)") (class "Default")
      (node (ref "CN1") (pin "17") (pinfunction "DDC/CEC_GND_17") (pintype "passive+no_connect"))
    )
    (net (code "70") (name "unconnected-(CN1-UTILITY-Pad14)") (class "Default")
      (node (ref "CN1") (pin "14") (pinfunction "UTILITY_14") (pintype "passive+no_connect"))
    )
    (net (code "71") (name "unconnected-(J1-NC-Pad7)") (class "Default")
      (node (ref "J1") (pin "7") (pinfunction "NC_7") (pintype "passive+no_connect"))
    )
    (net (code "72") (name "unconnected-(J1-Pad9)") (class "Default")
      (node (ref "J1") (pin "9") (pinfunction "9_9") (pintype "passive"))
    )
    (net (code "73") (name "unconnected-(J1-Pad10)") (class "Default")
      (node (ref "J1") (pin "10") (pinfunction "10_10") (pintype "passive"))
    )
    (net (code "74") (name "unconnected-(J1-Pad11)") (class "Default")
      (node (ref "J1") (pin "11") (pinfunction "11_11") (pintype "passive"))
    )
    (net (code "75") (name "unconnected-(J1-Pad12)") (class "Default")
      (node (ref "J1") (pin "12") (pinfunction "12_12") (pintype "passive"))
    )
    (net (code "76") (name "unconnected-(J1-PadSH1)") (class "Default")
      (node (ref "J1") (pin "SH1") (pinfunction "SH1_SH1") (pintype "passive"))
    )
    (net (code "77") (name "unconnected-(J1-PadSH2)") (class "Default")
      (node (ref "J1") (pin "SH2") (pinfunction "SH2_SH2") (pintype "passive"))
    )
    (net (code "78") (name "unconnected-(USB2-StdA_SSRX1+-Pad6)") (class "Default")
      (node (ref "USB2") (pin "6") (pinfunction "StdA_SSRX1+_6") (pintype "passive+no_connect"))
    )
    (net (code "79") (name "unconnected-(USB2-StdA_SSRX1--Pad5)") (class "Default")
      (node (ref "USB2") (pin "5") (pinfunction "StdA_SSRX1-_5") (pintype "passive+no_connect"))
    )
    (net (code "80") (name "unconnected-(USB2-StdA_SSRX2+-Pad15)") (class "Default")
      (node (ref "USB2") (pin "15") (pinfunction "StdA_SSRX2+_15") (pintype "passive+no_connect"))
    )
    (net (code "81") (name "unconnected-(USB2-StdA_SSRX2--Pad14)") (class "Default")
      (node (ref "USB2") (pin "14") (pinfunction "StdA_SSRX2-_14") (pintype "passive+no_connect"))
    )
    (net (code "82") (name "unconnected-(USB2-StdA_SSTX1+-Pad9)") (class "Default")
      (node (ref "USB2") (pin "9") (pinfunction "StdA_SSTX1+_9") (pintype "passive+no_connect"))
    )
    (net (code "83") (name "unconnected-(USB2-StdA_SSTX1--Pad8)") (class "Default")
      (node (ref "USB2") (pin "8") (pinfunction "StdA_SSTX1-_8") (pintype "passive+no_connect"))
    )
    (net (code "84") (name "unconnected-(USB2-StdA_SSTX2+-Pad18)") (class "Default")
      (node (ref "USB2") (pin "18") (pinfunction "StdA_SSTX2+_18") (pintype "passive+no_connect"))
    )
    (net (code "85") (name "unconnected-(USB2-StdA_SSTX2--Pad17)") (class "Default")
      (node (ref "USB2") (pin "17") (pinfunction "StdA_SSTX2-_17") (pintype "passive+no_connect"))
    )
    (net (code "86") (name "unconnected-(USB3-SBU1-Pad9)") (class "Default")
      (node (ref "USB3") (pin "9") (pinfunction "SBU1_9") (pintype "passive+no_connect"))
    )
    (net (code "87") (name "unconnected-(USB3-SBU2-Pad3)") (class "Default")
      (node (ref "USB3") (pin "3") (pinfunction "SBU2_3") (pintype "passive+no_connect"))
    )
  )
)
